# Stir_Plate.net
KiCad netlist of a schematic drawn in EAGLE
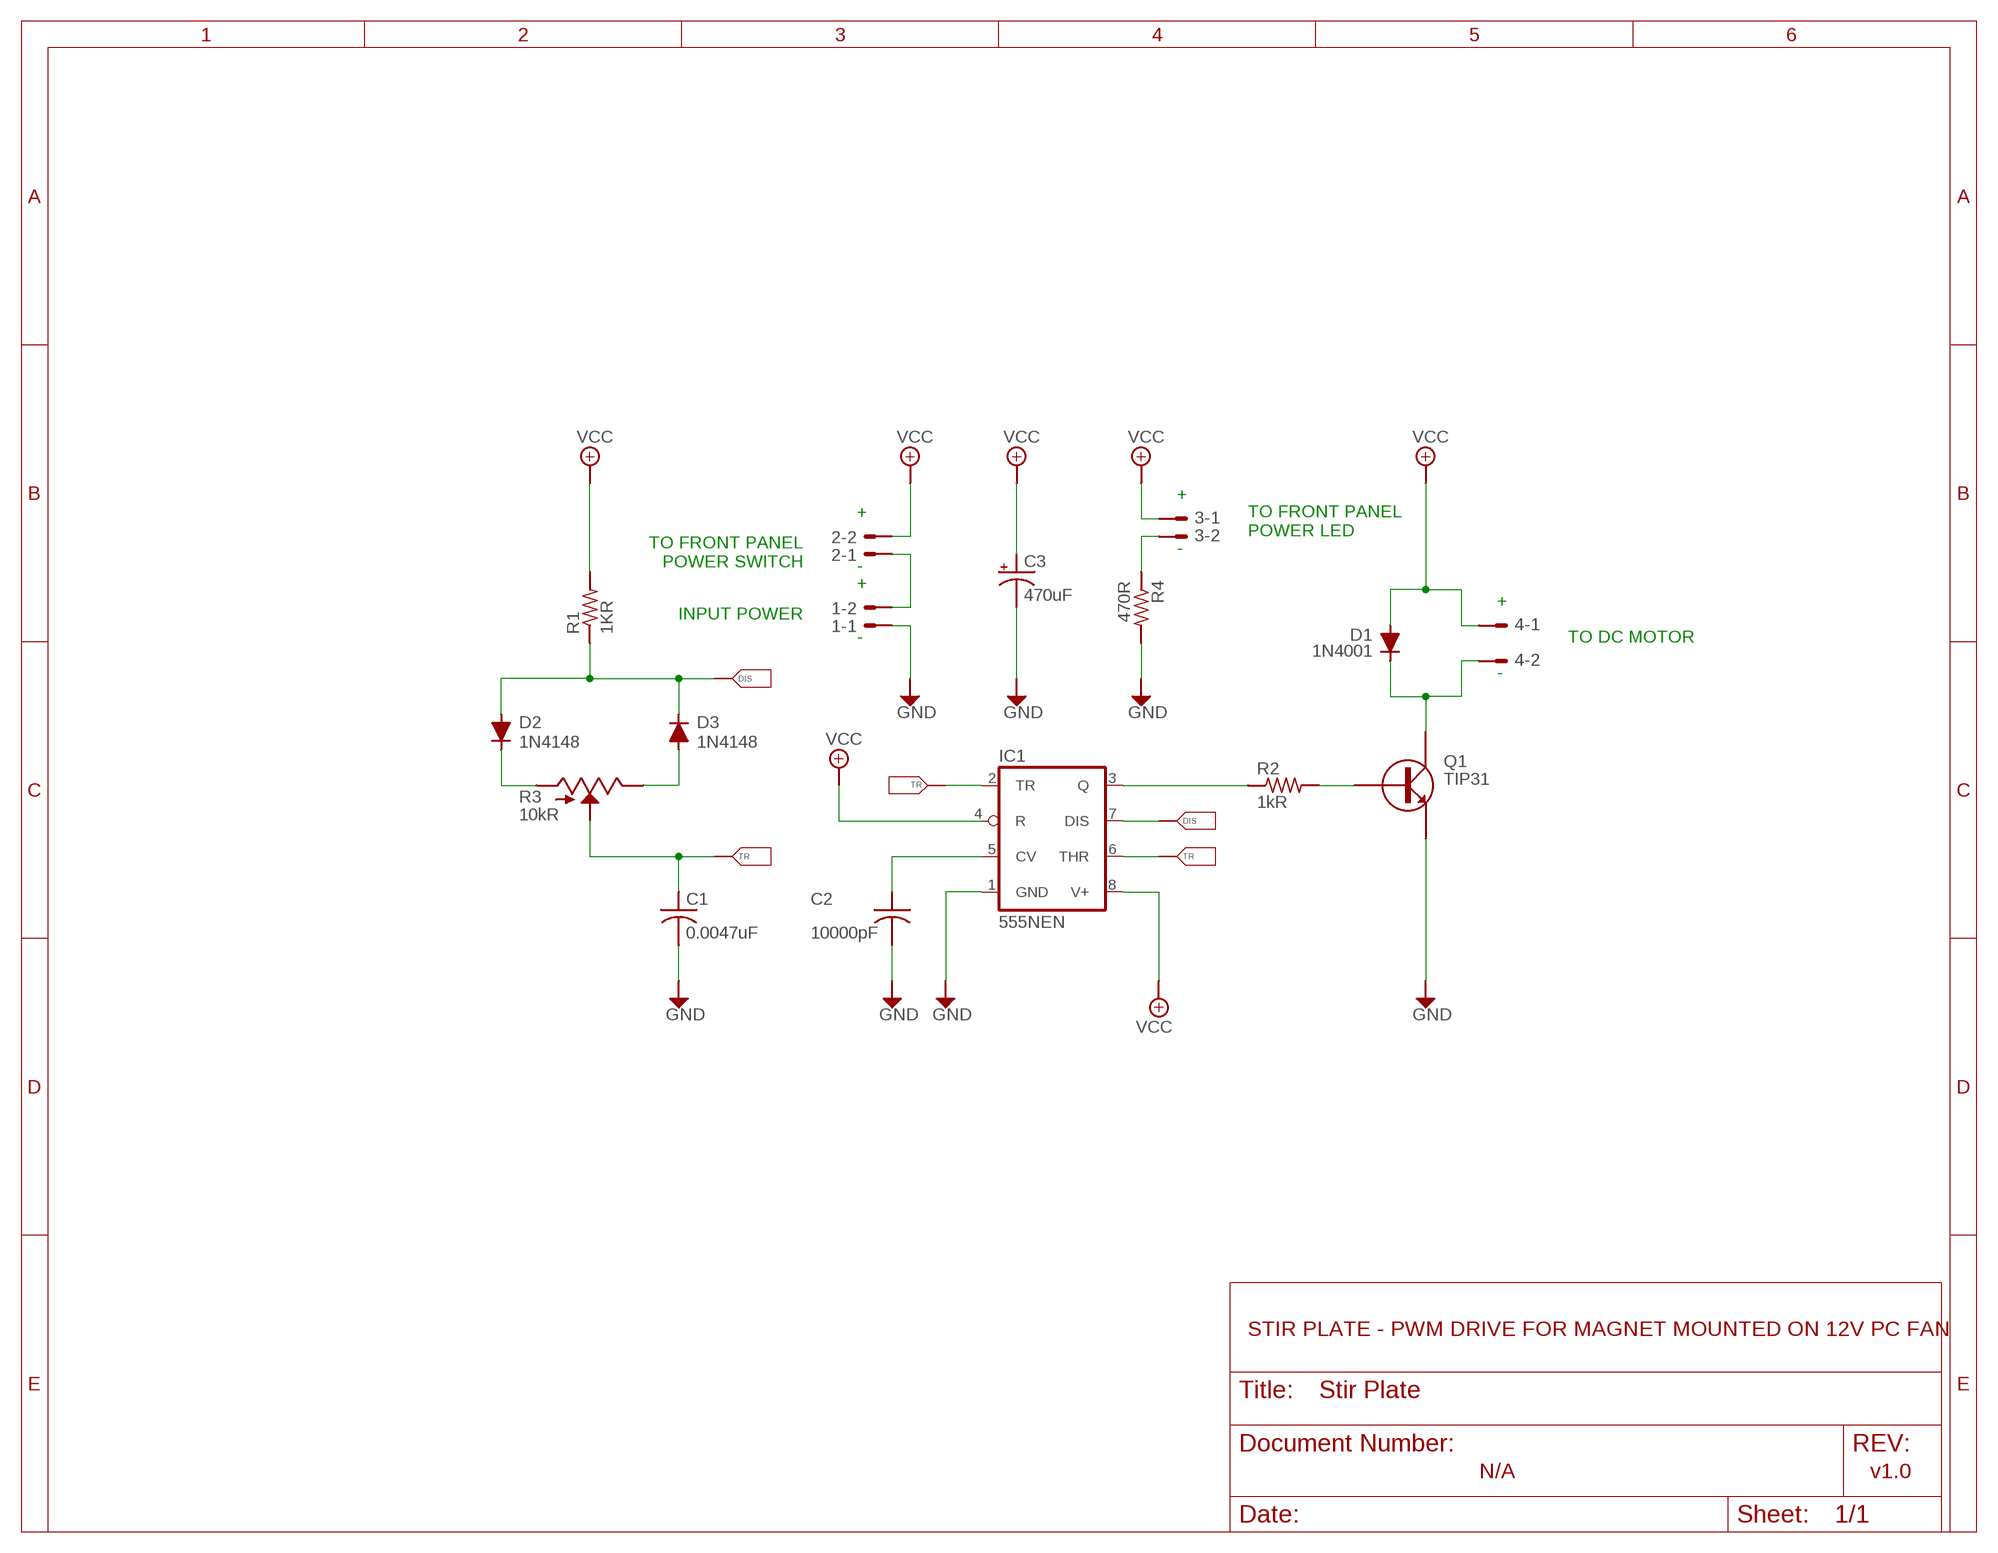
[diagram p0: schematic, sheet 1]

(export (version "E")
  (design (tool "Eeschema 10.0.6"))
  (components
    (comp (ref "1")
      (value "22-23-2021")
      (footprint "eagle-import:22-23-2021")
      (fields (field (name "MF") "MOLEX"))
      (libsource (lib "eagle-import") (part "22-23-2021"))
    )
    (comp (ref "2")
      (value "22-23-2021")
      (footprint "eagle-import:22-23-2021")
      (fields (field (name "MF") "MOLEX"))
      (libsource (lib "eagle-import") (part "22-23-2021"))
    )
    (comp (ref "3")
      (value "22-23-2021")
      (footprint "eagle-import:22-23-2021")
      (fields (field (name "MF") "MOLEX"))
      (libsource (lib "eagle-import") (part "22-23-2021"))
    )
    (comp (ref "4")
      (value "22-23-2021")
      (footprint "eagle-import:22-23-2021")
      (fields (field (name "MF") "MOLEX"))
      (libsource (lib "eagle-import") (part "22-23-2021"))
    )
    (comp (ref "C1")
      (value "0.0047uF")
      (footprint "eagle-import:C025-030X050")
      (libsource (lib "eagle-import") (part "C-US025-030X050"))
    )
    (comp (ref "C2")
      (value "10000pF")
      (footprint "eagle-import:C025-030X050")
      (libsource (lib "eagle-import") (part "C-US025-030X050"))
    )
    (comp (ref "C3")
      (value "470uF")
      (footprint "eagle-import:E2-5")
      (libsource (lib "eagle-import") (part "CPOL-USE2-5"))
    )
    (comp (ref "D1")
      (value "1N4001")
      (footprint "eagle-import:DO41-10")
      (libsource (lib "eagle-import") (part "1N4001"))
    )
    (comp (ref "D2")
      (value "1N4148")
      (footprint "eagle-import:DO35-7")
      (libsource (lib "eagle-import") (part "1N4148DO35-7"))
    )
    (comp (ref "D3")
      (value "1N4148")
      (footprint "eagle-import:DO35-7")
      (libsource (lib "eagle-import") (part "1N4148DO35-7"))
    )
    (comp (ref "FRAME1")
      (value "FRAME_A_L")
      (footprint "eagle-import:FRAME_A_L")
      (libsource (lib "eagle-import") (part "FRAME_A_L"))
    )
    (comp (ref "IC1")
      (value "555NEN")
      (footprint "eagle-import:DIL08")
      (libsource (lib "eagle-import") (part "555NNE"))
    )
    (comp (ref "Q1")
      (value "TIP31")
      (footprint "eagle-import:TO220AV")
      (libsource (lib "eagle-import") (part "TIP31"))
    )
    (comp (ref "R1")
      (value "1KR")
      (footprint "eagle-import:0207_10")
      (libsource (lib "eagle-import") (part "R-US_0207/10"))
    )
    (comp (ref "R2")
      (value "1kR")
      (footprint "eagle-import:0207_10")
      (libsource (lib "eagle-import") (part "R-US_0207/10"))
    )
    (comp (ref "R3")
      (value "10kR")
      (footprint "eagle-import:3RP_1610N")
      (libsource (lib "eagle-import") (part "TRIM_US-"))
    )
    (comp (ref "R4")
      (value "470R")
      (footprint "eagle-import:0207_10")
      (libsource (lib "eagle-import") (part "R-US_0207/10"))
    )
    (comp (ref "U$1")
      (value "DOCFIELD")
      (footprint "eagle-import:DOCFIELD")
      (libsource (lib "eagle-import") (part "DOCFIELD"))
    )
  )
  (nets
    (net (code "1") (name "/N$3") (class "Default")
      (node (ref "D2") (pin "A") (pinfunction "A_A") (pintype "passive"))
      (node (ref "D3") (pin "C") (pinfunction "C_C") (pintype "passive"))
      (node (ref "IC1") (pin "7") (pinfunction "DIS_7") (pintype "input"))
      (node (ref "R1") (pin "1") (pinfunction "1_1") (pintype "passive"))
    )
    (net (code "2") (name "/N$6") (class "Default")
      (node (ref "IC1") (pin "2") (pinfunction "TR_2") (pintype "input"))
      (node (ref "IC1") (pin "6") (pinfunction "THR_6") (pintype "input"))
    )
    (net (code "3") (name "GND") (class "Default")
      (node (ref "1") (pin "1") (pinfunction "S_1") (pintype "passive"))
      (node (ref "C1") (pin "2") (pinfunction "2_2") (pintype "passive"))
      (node (ref "C2") (pin "2") (pinfunction "2_2") (pintype "passive"))
      (node (ref "C3") (pin "-") (pinfunction "-_-") (pintype "passive"))
      (node (ref "IC1") (pin "1") (pinfunction "GND_1") (pintype "power_in"))
      (node (ref "Q1") (pin "E") (pinfunction "E_E") (pintype "passive"))
      (node (ref "R4") (pin "2") (pinfunction "2_2") (pintype "passive"))
    )
    (net (code "4") (name "Net-(1B-S)") (class "Default")
      (node (ref "1") (pin "2") (pinfunction "S_2") (pintype "passive"))
      (node (ref "2") (pin "1") (pinfunction "S_1") (pintype "passive"))
    )
    (net (code "5") (name "Net-(3B-S)") (class "Default")
      (node (ref "3") (pin "2") (pinfunction "S_2") (pintype "passive"))
      (node (ref "R4") (pin "1") (pinfunction "1_1") (pintype "passive"))
    )
    (net (code "6") (name "Net-(4B-S)") (class "Default")
      (node (ref "4") (pin "2") (pinfunction "S_2") (pintype "passive"))
      (node (ref "D1") (pin "C") (pinfunction "C_C") (pintype "passive"))
      (node (ref "Q1") (pin "C") (pinfunction "C_C") (pintype "passive"))
    )
    (net (code "7") (name "Net-(IC1-CV)") (class "Default")
      (node (ref "C2") (pin "1") (pinfunction "1_1") (pintype "passive"))
      (node (ref "IC1") (pin "5") (pinfunction "CV_5") (pintype "input"))
    )
    (net (code "8") (name "Net-(IC1-Q)") (class "Default")
      (node (ref "IC1") (pin "3") (pinfunction "Q_3") (pintype "output"))
      (node (ref "R2") (pin "1") (pinfunction "1_1") (pintype "passive"))
    )
    (net (code "9") (name "Net-(Q1-PadB)") (class "Default")
      (node (ref "Q1") (pin "B") (pinfunction "B_B") (pintype "passive"))
      (node (ref "R2") (pin "2") (pinfunction "2_2") (pintype "passive"))
    )
    (net (code "10") (name "Net-(R3-A)") (class "Default")
      (node (ref "D2") (pin "C") (pinfunction "C_C") (pintype "passive"))
      (node (ref "R3") (pin "1") (pinfunction "A_1") (pintype "passive"))
    )
    (net (code "11") (name "Net-(R3-E)") (class "Default")
      (node (ref "D3") (pin "A") (pinfunction "A_A") (pintype "passive"))
      (node (ref "R3") (pin "2") (pinfunction "E_2") (pintype "passive"))
    )
    (net (code "12") (name "Net-(R3-S)") (class "Default")
      (node (ref "C1") (pin "1") (pinfunction "1_1") (pintype "passive"))
      (node (ref "R3") (pin "3") (pinfunction "S_3") (pintype "passive"))
    )
    (net (code "13") (name "VCC") (class "Default")
      (node (ref "2") (pin "2") (pinfunction "S_2") (pintype "passive"))
      (node (ref "3") (pin "1") (pinfunction "S_1") (pintype "passive"))
      (node (ref "4") (pin "1") (pinfunction "S_1") (pintype "passive"))
      (node (ref "C3") (pin "+") (pinfunction "+_+") (pintype "passive"))
      (node (ref "D1") (pin "A") (pinfunction "A_A") (pintype "passive"))
      (node (ref "IC1") (pin "4") (pinfunction "R_4") (pintype "input"))
      (node (ref "IC1") (pin "8") (pinfunction "V+_8") (pintype "power_in"))
      (node (ref "R1") (pin "2") (pinfunction "2_2") (pintype "passive"))
    )
  )
)
